# basestation.net
KiCad netlist of a schematic drawn in EAGLE
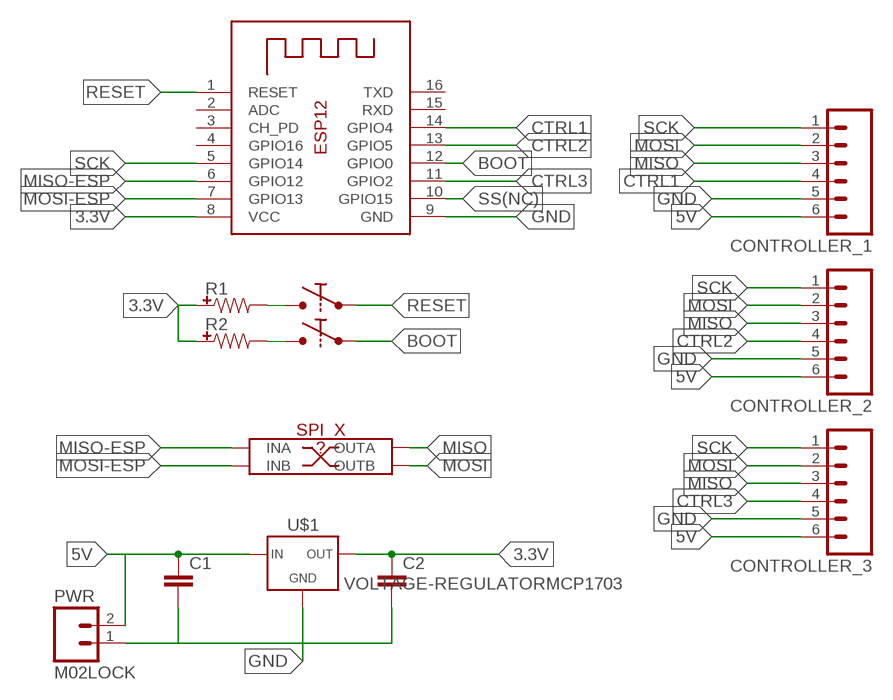
[diagram p0: schematic, sheet 1]

(export (version "E")
  (design (tool "Eeschema 10.0.6"))
  (components
    (comp (ref "BOOT")
      (value "BUTTONPJRC")
      (footprint "eagle-import:BUTTON-PJRC")
      (libsource (lib "eagle-import") (part "BUTTONPJRC"))
    )
    (comp (ref "C1")
      (value "CAPUNIVERSAL")
      (footprint "eagle-import:0402-0603-0805-UNIVERSAL")
      (libsource (lib "eagle-import") (part "CAPUNIVERSAL"))
    )
    (comp (ref "C2")
      (value "CAPUNIVERSAL")
      (footprint "eagle-import:0402-0603-0805-UNIVERSAL")
      (libsource (lib "eagle-import") (part "CAPUNIVERSAL"))
    )
    (comp (ref "CONTROLLER_1")
      (value "M06LOCK")
      (footprint "eagle-import:1X06_LOCK")
      (libsource (lib "eagle-import") (part "M06LOCK"))
    )
    (comp (ref "CONTROLLER_2")
      (value "M06LOCK")
      (footprint "eagle-import:1X06_LOCK")
      (libsource (lib "eagle-import") (part "M06LOCK"))
    )
    (comp (ref "CONTROLLER_3")
      (value "M06LOCK")
      (footprint "eagle-import:1X06_LOCK")
      (libsource (lib "eagle-import") (part "M06LOCK"))
    )
    (comp (ref "PWR")
      (value "M02LOCK")
      (footprint "eagle-import:1X02_LOCK")
      (libsource (lib "eagle-import") (part "M02LOCK"))
    )
    (comp (ref "R1")
      (value "RESISTORUNIVERSAL")
      (footprint "eagle-import:0402-0603-0805-UNIVERSAL")
      (libsource (lib "eagle-import") (part "RESISTORUNIVERSAL"))
    )
    (comp (ref "R2")
      (value "RESISTORUNIVERSAL")
      (footprint "eagle-import:0402-0603-0805-UNIVERSAL")
      (libsource (lib "eagle-import") (part "RESISTORUNIVERSAL"))
    )
    (comp (ref "RESET")
      (value "BUTTONPJRC")
      (footprint "eagle-import:BUTTON-PJRC")
      (libsource (lib "eagle-import") (part "BUTTONPJRC"))
    )
    (comp (ref "SPI_X")
      (value "UART_SWITCHER0603")
      (footprint "eagle-import:UART_SWITCHER_0603")
      (libsource (lib "eagle-import") (part "UART_SWITCHER0603"))
    )
    (comp (ref "U$1")
      (value "VOLTAGE-REGULATORMCP1703")
      (footprint "eagle-import:SOT23")
      (libsource (lib "eagle-import") (part "VOLTAGE-REGULATORMCP1703"))
    )
    (comp (ref "X1")
      (value "ESP-12")
      (footprint "eagle-import:ESP-12")
      (libsource (lib "eagle-import") (part "ESP-12"))
    )
  )
  (nets
    (net (code "1") (name "3.3V") (class "Default")
      (node (ref "C2") (pin "-") (pinfunction "1_-") (pintype "passive"))
      (node (ref "R1") (pin "-") (pinfunction "1_-") (pintype "passive"))
      (node (ref "R2") (pin "-") (pinfunction "1_-") (pintype "passive"))
      (node (ref "U$1") (pin "2") (pinfunction "OUT_2") (pintype "input"))
      (node (ref "X1") (pin "8") (pinfunction "VCC_8") (pintype "power_in"))
    )
    (net (code "2") (name "5V") (class "Default")
      (node (ref "C1") (pin "-") (pinfunction "1_-") (pintype "passive"))
      (node (ref "CONTROLLER_1") (pin "6") (pinfunction "6_6") (pintype "passive"))
      (node (ref "CONTROLLER_2") (pin "6") (pinfunction "6_6") (pintype "passive"))
      (node (ref "CONTROLLER_3") (pin "6") (pinfunction "6_6") (pintype "passive"))
      (node (ref "PWR") (pin "2") (pinfunction "2_2") (pintype "passive"))
      (node (ref "U$1") (pin "3") (pinfunction "IN_3") (pintype "input"))
    )
    (net (code "3") (name "BOOT") (class "Default")
      (node (ref "BOOT") (pin "B1") (pinfunction "P$2_B1") (pintype "bidirectional"))
      (node (ref "BOOT") (pin "B2") (pinfunction "P$2_B2") (pintype "bidirectional"))
      (node (ref "X1") (pin "12") (pinfunction "GPIO0_12") (pintype "bidirectional"))
    )
    (net (code "4") (name "CTRL1") (class "Default")
      (node (ref "CONTROLLER_1") (pin "4") (pinfunction "4_4") (pintype "passive"))
      (node (ref "X1") (pin "14") (pinfunction "GPIO4_14") (pintype "bidirectional"))
    )
    (net (code "5") (name "CTRL2") (class "Default")
      (node (ref "CONTROLLER_2") (pin "4") (pinfunction "4_4") (pintype "passive"))
      (node (ref "X1") (pin "13") (pinfunction "GPIO5_13") (pintype "bidirectional"))
    )
    (net (code "6") (name "CTRL3") (class "Default")
      (node (ref "CONTROLLER_3") (pin "4") (pinfunction "4_4") (pintype "passive"))
      (node (ref "X1") (pin "11") (pinfunction "GPIO2_11") (pintype "bidirectional"))
    )
    (net (code "7") (name "GND") (class "Default")
      (node (ref "C1") (pin "+") (pinfunction "2_+") (pintype "passive"))
      (node (ref "C2") (pin "+") (pinfunction "2_+") (pintype "passive"))
      (node (ref "CONTROLLER_1") (pin "5") (pinfunction "5_5") (pintype "passive"))
      (node (ref "CONTROLLER_2") (pin "5") (pinfunction "5_5") (pintype "passive"))
      (node (ref "CONTROLLER_3") (pin "5") (pinfunction "5_5") (pintype "passive"))
      (node (ref "PWR") (pin "1") (pinfunction "1_1") (pintype "passive"))
      (node (ref "U$1") (pin "1") (pinfunction "GND_1") (pintype "input"))
      (node (ref "X1") (pin "9") (pinfunction "GND_9") (pintype "power_in"))
    )
    (net (code "8") (name "MISO") (class "Default")
      (node (ref "CONTROLLER_1") (pin "3") (pinfunction "3_3") (pintype "passive"))
      (node (ref "CONTROLLER_2") (pin "3") (pinfunction "3_3") (pintype "passive"))
      (node (ref "CONTROLLER_3") (pin "3") (pinfunction "3_3") (pintype "passive"))
      (node (ref "SPI_X") (pin "RX_B") (pinfunction "OUTA_RX_B") (pintype "bidirectional"))
    )
    (net (code "9") (name "MISO-ESP") (class "Default")
      (node (ref "SPI_X") (pin "TX_A") (pinfunction "INA_TX_A") (pintype "bidirectional"))
      (node (ref "X1") (pin "6") (pinfunction "GPIO12_6") (pintype "bidirectional"))
    )
    (net (code "10") (name "MOSI") (class "Default")
      (node (ref "CONTROLLER_1") (pin "2") (pinfunction "2_2") (pintype "passive"))
      (node (ref "CONTROLLER_2") (pin "2") (pinfunction "2_2") (pintype "passive"))
      (node (ref "CONTROLLER_3") (pin "2") (pinfunction "2_2") (pintype "passive"))
      (node (ref "SPI_X") (pin "TX_B") (pinfunction "OUTB_TX_B") (pintype "bidirectional"))
    )
    (net (code "11") (name "MOSI-ESP") (class "Default")
      (node (ref "SPI_X") (pin "RX_A") (pinfunction "INB_RX_A") (pintype "bidirectional"))
      (node (ref "X1") (pin "7") (pinfunction "GPIO13_7") (pintype "bidirectional"))
    )
    (net (code "12") (name "Net-(R1-2)") (class "Default")
      (node (ref "R1") (pin "+") (pinfunction "2_+") (pintype "passive"))
      (node (ref "RESET") (pin "A1") (pinfunction "P$1_A1") (pintype "bidirectional"))
      (node (ref "RESET") (pin "A2") (pinfunction "P$1_A2") (pintype "bidirectional"))
    )
    (net (code "13") (name "Net-(R2-2)") (class "Default")
      (node (ref "BOOT") (pin "A1") (pinfunction "P$1_A1") (pintype "bidirectional"))
      (node (ref "BOOT") (pin "A2") (pinfunction "P$1_A2") (pintype "bidirectional"))
      (node (ref "R2") (pin "+") (pinfunction "2_+") (pintype "passive"))
    )
    (net (code "14") (name "RESET") (class "Default")
      (node (ref "RESET") (pin "B1") (pinfunction "P$2_B1") (pintype "bidirectional"))
      (node (ref "RESET") (pin "B2") (pinfunction "P$2_B2") (pintype "bidirectional"))
      (node (ref "X1") (pin "1") (pinfunction "RESET_1") (pintype "input"))
    )
    (net (code "15") (name "SCK") (class "Default")
      (node (ref "CONTROLLER_1") (pin "1") (pinfunction "1_1") (pintype "passive"))
      (node (ref "CONTROLLER_2") (pin "1") (pinfunction "1_1") (pintype "passive"))
      (node (ref "CONTROLLER_3") (pin "1") (pinfunction "1_1") (pintype "passive"))
      (node (ref "X1") (pin "5") (pinfunction "GPIO14_5") (pintype "bidirectional"))
    )
    (net (code "16") (name "SS(NC)") (class "Default")
      (node (ref "X1") (pin "10") (pinfunction "GPIO15_10") (pintype "bidirectional"))
    )
    (net (code "17") (name "unconnected-(X1-ADC-Pad2)") (class "Default")
      (node (ref "X1") (pin "2") (pinfunction "ADC_2") (pintype "passive"))
    )
    (net (code "18") (name "unconnected-(X1-CH_PD-Pad3)") (class "Default")
      (node (ref "X1") (pin "3") (pinfunction "CH_PD_3") (pintype "input"))
    )
    (net (code "19") (name "unconnected-(X1-GPIO16-Pad4)") (class "Default")
      (node (ref "X1") (pin "4") (pinfunction "GPIO16_4") (pintype "bidirectional"))
    )
    (net (code "20") (name "unconnected-(X1-RXD-Pad15)") (class "Default")
      (node (ref "X1") (pin "15") (pinfunction "RXD_15") (pintype "input"))
    )
    (net (code "21") (name "unconnected-(X1-TXD-Pad16)") (class "Default")
      (node (ref "X1") (pin "16") (pinfunction "TXD_16") (pintype "output"))
    )
  )
)
